# ASL2002.net
KiCad netlist of a schematic drawn in EAGLE
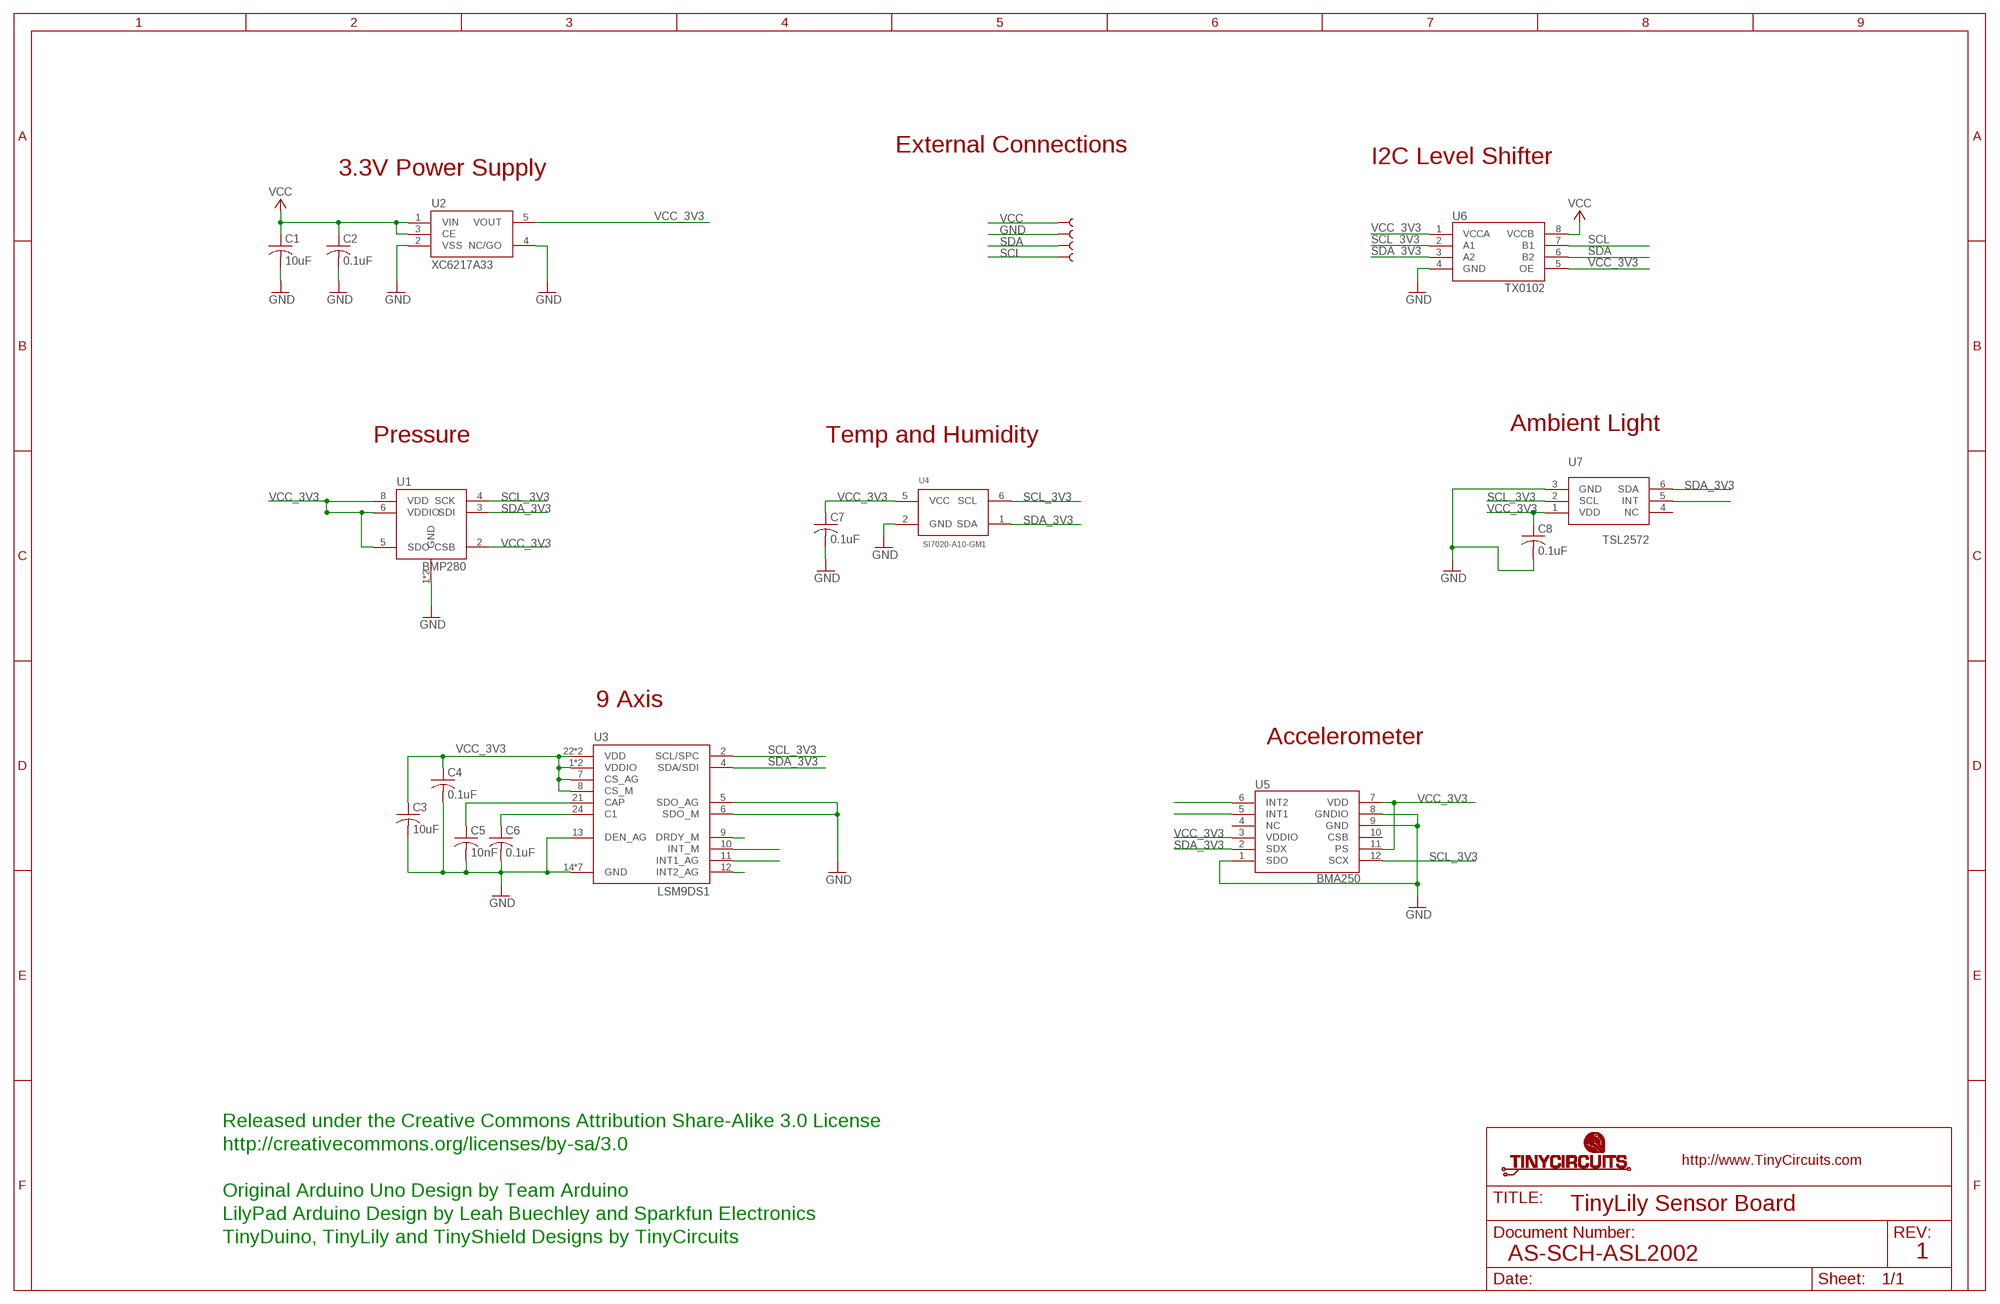
[diagram p0: schematic, sheet 1]

(export (version "E")
  (design (tool "Eeschema 10.0.6"))
  (components
    (comp (ref "$1")
      (value "SEWTAB")
      (footprint "eagle-import:SEWTAP_TH")
      (libsource (lib "eagle-import") (part "SEWTAB"))
    )
    (comp (ref "C1")
      (value "10uF")
      (footprint "eagle-import:C0603")
      (fields (field (name "PARTNO") "AS-ITM-00002"))
      (libsource (lib "eagle-import") (part "AS-ITM-00002"))
    )
    (comp (ref "C2")
      (value "0.1uF")
      (footprint "eagle-import:C0402")
      (fields (field (name "PARTNO") "AS-ITM-00008") (field (name "PARTNO_1") "AS-ITM-00008"))
      (libsource (lib "eagle-import") (part "AS-ITM-00008"))
    )
    (comp (ref "C3")
      (value "10uF")
      (footprint "eagle-import:C0603")
      (fields (field (name "PARTNO") "AS-ITM-00002") (field (name "PARTNO_1") "AS-ITM-00002"))
      (libsource (lib "eagle-import") (part "AS-ITM-00002"))
    )
    (comp (ref "C4")
      (value "0.1uF")
      (footprint "eagle-import:C0402")
      (fields (field (name "PARTNO") "AS-ITM-00008") (field (name "PARTNO_1") "AS-ITM-00008"))
      (libsource (lib "eagle-import") (part "AS-ITM-00008"))
    )
    (comp (ref "C5")
      (value "10nF")
      (footprint "eagle-import:C0402")
      (fields (field (name "PARTNO") "AS-ITM-00084"))
      (libsource (lib "eagle-import") (part "AS-ITM-00084"))
    )
    (comp (ref "C6")
      (value "0.1uF")
      (footprint "eagle-import:C0402")
      (fields (field (name "PARTNO") "AS-ITM-00008"))
      (libsource (lib "eagle-import") (part "AS-ITM-00008"))
    )
    (comp (ref "C7")
      (value "0.1uF")
      (footprint "eagle-import:C0402")
      (fields (field (name "PARTNO") "AS-ITM-00008") (field (name "PARTNO_1") "AS-ITM-00008"))
      (libsource (lib "eagle-import") (part "AS-ITM-00008"))
    )
    (comp (ref "C8")
      (value "0.1uF")
      (footprint "eagle-import:C0402")
      (fields (field (name "PARTNO") "AS-ITM-00008") (field (name "PARTNO_1") "AS-ITM-00008"))
      (libsource (lib "eagle-import") (part "AS-ITM-00008"))
    )
    (comp (ref "U$1")
      (value "SEWTAB")
      (footprint "eagle-import:SEWTAP_TH")
      (libsource (lib "eagle-import") (part "SEWTAB"))
    )
    (comp (ref "U$2")
      (value "SEWTAB")
      (footprint "eagle-import:SEWTAP_TH")
      (libsource (lib "eagle-import") (part "SEWTAB"))
    )
    (comp (ref "U$3")
      (value "SEWTAB")
      (footprint "eagle-import:SEWTAP_TH")
      (libsource (lib "eagle-import") (part "SEWTAB"))
    )
    (comp (ref "U1")
      (value "BMP280")
      (footprint "eagle-import:BMP280")
      (fields (field (name "PARTNO") "AS-ITM-00264"))
      (libsource (lib "eagle-import") (part "AS-ITM-00264"))
    )
    (comp (ref "U2")
      (value "XC6217A33")
      (footprint "eagle-import:SOT-25")
      (fields (field (name "PARTNO") "AS-ITM-00249") (field (name "PARTNO_1") "AS-ITM-00249"))
      (libsource (lib "eagle-import") (part "AS-ITM-00249"))
    )
    (comp (ref "U3")
      (value "LSM9DS1")
      (footprint "eagle-import:LGA-24")
      (fields (field (name "PARTNO") "AS-ITM-00265"))
      (libsource (lib "eagle-import") (part "AS-ITM-00265"))
    )
    (comp (ref "U4")
      (value "SI7020-A10-GM1")
      (footprint "eagle-import:DFN6")
      (fields (field (name "PARTNO") "AS-ITM-00218"))
      (libsource (lib "eagle-import") (part "AS-ITM-00218"))
    )
    (comp (ref "U5")
      (value "BMA250")
      (footprint "eagle-import:3-AXIS_ACCELEROMETER")
      (fields (field (name "PARTNO") "AS-ITM-00070"))
      (libsource (lib "eagle-import") (part "AS-ITM-00070"))
    )
    (comp (ref "U6")
      (value "TX0102")
      (footprint "eagle-import:DQE(R-PX2SON-N8)")
      (fields (field (name "PARTNO") "AS-ITM-00073"))
      (libsource (lib "eagle-import") (part "AS-ITM-00073"))
    )
    (comp (ref "U7")
      (value "TSL2572")
      (footprint "eagle-import:TSL2572")
      (fields (field (name "PARTNO") "AS-ITM-00116"))
      (libsource (lib "eagle-import") (part "AS-ITM-00116"))
    )
  )
  (nets
    (net (code "1") (name "/SCL") (class "Default")
      (node (ref "U$3") (pin "1") (pinfunction "1_1") (pintype "bidirectional"))
      (node (ref "U6") (pin "7") (pinfunction "B1_7") (pintype "bidirectional"))
    )
    (net (code "2") (name "/SCL_3V3") (class "Default")
      (node (ref "U1") (pin "4") (pinfunction "SCK_4") (pintype "bidirectional"))
      (node (ref "U3") (pin "2") (pinfunction "SCL/SPC_2") (pintype "bidirectional"))
      (node (ref "U4") (pin "6") (pinfunction "SCL_6") (pintype "bidirectional"))
      (node (ref "U5") (pin "12") (pinfunction "SCX_12") (pintype "bidirectional"))
      (node (ref "U6") (pin "2") (pinfunction "A1_2") (pintype "bidirectional"))
      (node (ref "U7") (pin "2") (pinfunction "SCL_2") (pintype "bidirectional"))
    )
    (net (code "3") (name "/SDA") (class "Default")
      (node (ref "U$2") (pin "1") (pinfunction "1_1") (pintype "bidirectional"))
      (node (ref "U6") (pin "6") (pinfunction "B2_6") (pintype "bidirectional"))
    )
    (net (code "4") (name "/SDA_3V3") (class "Default")
      (node (ref "U1") (pin "3") (pinfunction "SDI_3") (pintype "bidirectional"))
      (node (ref "U3") (pin "4") (pinfunction "SDA/SDI_4") (pintype "bidirectional"))
      (node (ref "U4") (pin "1") (pinfunction "SDA_1") (pintype "bidirectional"))
      (node (ref "U5") (pin "2") (pinfunction "SDX_2") (pintype "bidirectional"))
      (node (ref "U6") (pin "3") (pinfunction "A2_3") (pintype "bidirectional"))
      (node (ref "U7") (pin "6") (pinfunction "SDA_6") (pintype "bidirectional"))
    )
    (net (code "5") (name "/VCC_3V3") (class "Default")
      (node (ref "C3") (pin "1") (pinfunction "1_1") (pintype "passive"))
      (node (ref "C4") (pin "1") (pinfunction "1_1") (pintype "passive"))
      (node (ref "C7") (pin "1") (pinfunction "1_1") (pintype "passive"))
      (node (ref "C8") (pin "1") (pinfunction "1_1") (pintype "passive"))
      (node (ref "U1") (pin "2") (pinfunction "CSB_2") (pintype "bidirectional"))
      (node (ref "U1") (pin "5") (pinfunction "SDO_5") (pintype "bidirectional"))
      (node (ref "U1") (pin "6") (pinfunction "VDDIO_6") (pintype "bidirectional"))
      (node (ref "U1") (pin "8") (pinfunction "VDD_8") (pintype "bidirectional"))
      (node (ref "U2") (pin "5") (pinfunction "VOUT_5") (pintype "bidirectional"))
      (node (ref "U3") (pin "1") (pinfunction "VDDIO_1") (pintype "bidirectional"))
      (node (ref "U3") (pin "22") (pinfunction "VDD_22") (pintype "bidirectional"))
      (node (ref "U3") (pin "23") (pinfunction "VDD_23") (pintype "bidirectional"))
      (node (ref "U3") (pin "3") (pinfunction "VDDIO_3") (pintype "bidirectional"))
      (node (ref "U3") (pin "7") (pinfunction "CS_AG_7") (pintype "bidirectional"))
      (node (ref "U3") (pin "8") (pinfunction "CS_M_8") (pintype "bidirectional"))
      (node (ref "U4") (pin "5") (pinfunction "VCC_5") (pintype "bidirectional"))
      (node (ref "U5") (pin "11") (pinfunction "PS_11") (pintype "bidirectional"))
      (node (ref "U5") (pin "3") (pinfunction "VDDIO_3") (pintype "bidirectional"))
      (node (ref "U5") (pin "7") (pinfunction "VDD_7") (pintype "bidirectional"))
      (node (ref "U6") (pin "1") (pinfunction "VCCA_1") (pintype "bidirectional"))
      (node (ref "U6") (pin "5") (pinfunction "OE_5") (pintype "bidirectional"))
      (node (ref "U7") (pin "1") (pinfunction "VDD_1") (pintype "bidirectional"))
    )
    (net (code "6") (name "GND") (class "Default")
      (node (ref "C1") (pin "2") (pinfunction "2_2") (pintype "passive"))
      (node (ref "C2") (pin "2") (pinfunction "2_2") (pintype "passive"))
      (node (ref "C3") (pin "2") (pinfunction "2_2") (pintype "passive"))
      (node (ref "C4") (pin "2") (pinfunction "2_2") (pintype "passive"))
      (node (ref "C5") (pin "2") (pinfunction "2_2") (pintype "passive"))
      (node (ref "C6") (pin "2") (pinfunction "2_2") (pintype "passive"))
      (node (ref "C7") (pin "2") (pinfunction "2_2") (pintype "passive"))
      (node (ref "C8") (pin "2") (pinfunction "2_2") (pintype "passive"))
      (node (ref "U$1") (pin "1") (pinfunction "1_1") (pintype "bidirectional"))
      (node (ref "U1") (pin "1") (pinfunction "GND_1") (pintype "bidirectional"))
      (node (ref "U1") (pin "7") (pinfunction "GND_7") (pintype "bidirectional"))
      (node (ref "U2") (pin "2") (pinfunction "VSS_2") (pintype "power_in"))
      (node (ref "U2") (pin "4") (pinfunction "NC/GO_4") (pintype "bidirectional"))
      (node (ref "U3") (pin "13") (pinfunction "DEN_AG_13") (pintype "bidirectional"))
      (node (ref "U3") (pin "14") (pinfunction "GND_14") (pintype "bidirectional"))
      (node (ref "U3") (pin "15") (pinfunction "GND_15") (pintype "bidirectional"))
      (node (ref "U3") (pin "16") (pinfunction "GND_16") (pintype "bidirectional"))
      (node (ref "U3") (pin "17") (pinfunction "GND_17") (pintype "bidirectional"))
      (node (ref "U3") (pin "18") (pinfunction "GND_18") (pintype "bidirectional"))
      (node (ref "U3") (pin "19") (pinfunction "GND_19") (pintype "bidirectional"))
      (node (ref "U3") (pin "20") (pinfunction "GND_20") (pintype "bidirectional"))
      (node (ref "U3") (pin "5") (pinfunction "SDO_AG_5") (pintype "bidirectional"))
      (node (ref "U3") (pin "6") (pinfunction "SDO_M_6") (pintype "bidirectional"))
      (node (ref "U4") (pin "2") (pinfunction "GND_2") (pintype "bidirectional"))
      (node (ref "U5") (pin "1") (pinfunction "SDO_1") (pintype "bidirectional"))
      (node (ref "U5") (pin "8") (pinfunction "GNDIO_8") (pintype "bidirectional"))
      (node (ref "U5") (pin "9") (pinfunction "GND_9") (pintype "bidirectional"))
      (node (ref "U6") (pin "4") (pinfunction "GND_4") (pintype "bidirectional"))
      (node (ref "U7") (pin "3") (pinfunction "GND_3") (pintype "bidirectional"))
    )
    (net (code "7") (name "Net-(U3-C1)") (class "Default")
      (node (ref "C6") (pin "1") (pinfunction "1_1") (pintype "passive"))
      (node (ref "U3") (pin "24") (pinfunction "C1_24") (pintype "bidirectional"))
    )
    (net (code "8") (name "Net-(U3-CAP)") (class "Default")
      (node (ref "C5") (pin "1") (pinfunction "1_1") (pintype "passive"))
      (node (ref "U3") (pin "21") (pinfunction "CAP_21") (pintype "bidirectional"))
    )
    (net (code "9") (name "VCC") (class "Default")
      (node (ref "$1") (pin "1") (pinfunction "1_1") (pintype "bidirectional"))
      (node (ref "C1") (pin "1") (pinfunction "1_1") (pintype "passive"))
      (node (ref "C2") (pin "1") (pinfunction "1_1") (pintype "passive"))
      (node (ref "U2") (pin "1") (pinfunction "VIN_1") (pintype "bidirectional"))
      (node (ref "U2") (pin "3") (pinfunction "CE_3") (pintype "bidirectional"))
      (node (ref "U6") (pin "8") (pinfunction "VCCB_8") (pintype "bidirectional"))
    )
    (net (code "10") (name "unconnected-(U3-DRDY_M-Pad9)") (class "Default")
      (node (ref "U3") (pin "9") (pinfunction "DRDY_M_9") (pintype "bidirectional"))
    )
    (net (code "11") (name "unconnected-(U3-INT1_AG-Pad11)") (class "Default")
      (node (ref "U3") (pin "11") (pinfunction "INT1_AG_11") (pintype "bidirectional"))
    )
    (net (code "12") (name "unconnected-(U3-INT2_AG-Pad12)") (class "Default")
      (node (ref "U3") (pin "12") (pinfunction "INT2_AG_12") (pintype "bidirectional"))
    )
    (net (code "13") (name "unconnected-(U3-INT_M-Pad10)") (class "Default")
      (node (ref "U3") (pin "10") (pinfunction "INT_M_10") (pintype "bidirectional"))
    )
    (net (code "14") (name "unconnected-(U5-CSB-Pad10)") (class "Default")
      (node (ref "U5") (pin "10") (pinfunction "CSB_10") (pintype "bidirectional"))
    )
    (net (code "15") (name "unconnected-(U5-INT1-Pad5)") (class "Default")
      (node (ref "U5") (pin "5") (pinfunction "INT1_5") (pintype "bidirectional"))
    )
    (net (code "16") (name "unconnected-(U5-INT2-Pad6)") (class "Default")
      (node (ref "U5") (pin "6") (pinfunction "INT2_6") (pintype "bidirectional"))
    )
    (net (code "17") (name "unconnected-(U5-NC-Pad4)") (class "Default")
      (node (ref "U5") (pin "4") (pinfunction "NC_4") (pintype "bidirectional"))
    )
    (net (code "18") (name "unconnected-(U7-INT-Pad5)") (class "Default")
      (node (ref "U7") (pin "5") (pinfunction "INT_5") (pintype "bidirectional"))
    )
    (net (code "19") (name "unconnected-(U7-NC-Pad4)") (class "Default")
      (node (ref "U7") (pin "4") (pinfunction "NC_4") (pintype "bidirectional"))
    )
  )
)
